# razniffer.net
KiCad netlist of a schematic drawn in EAGLE
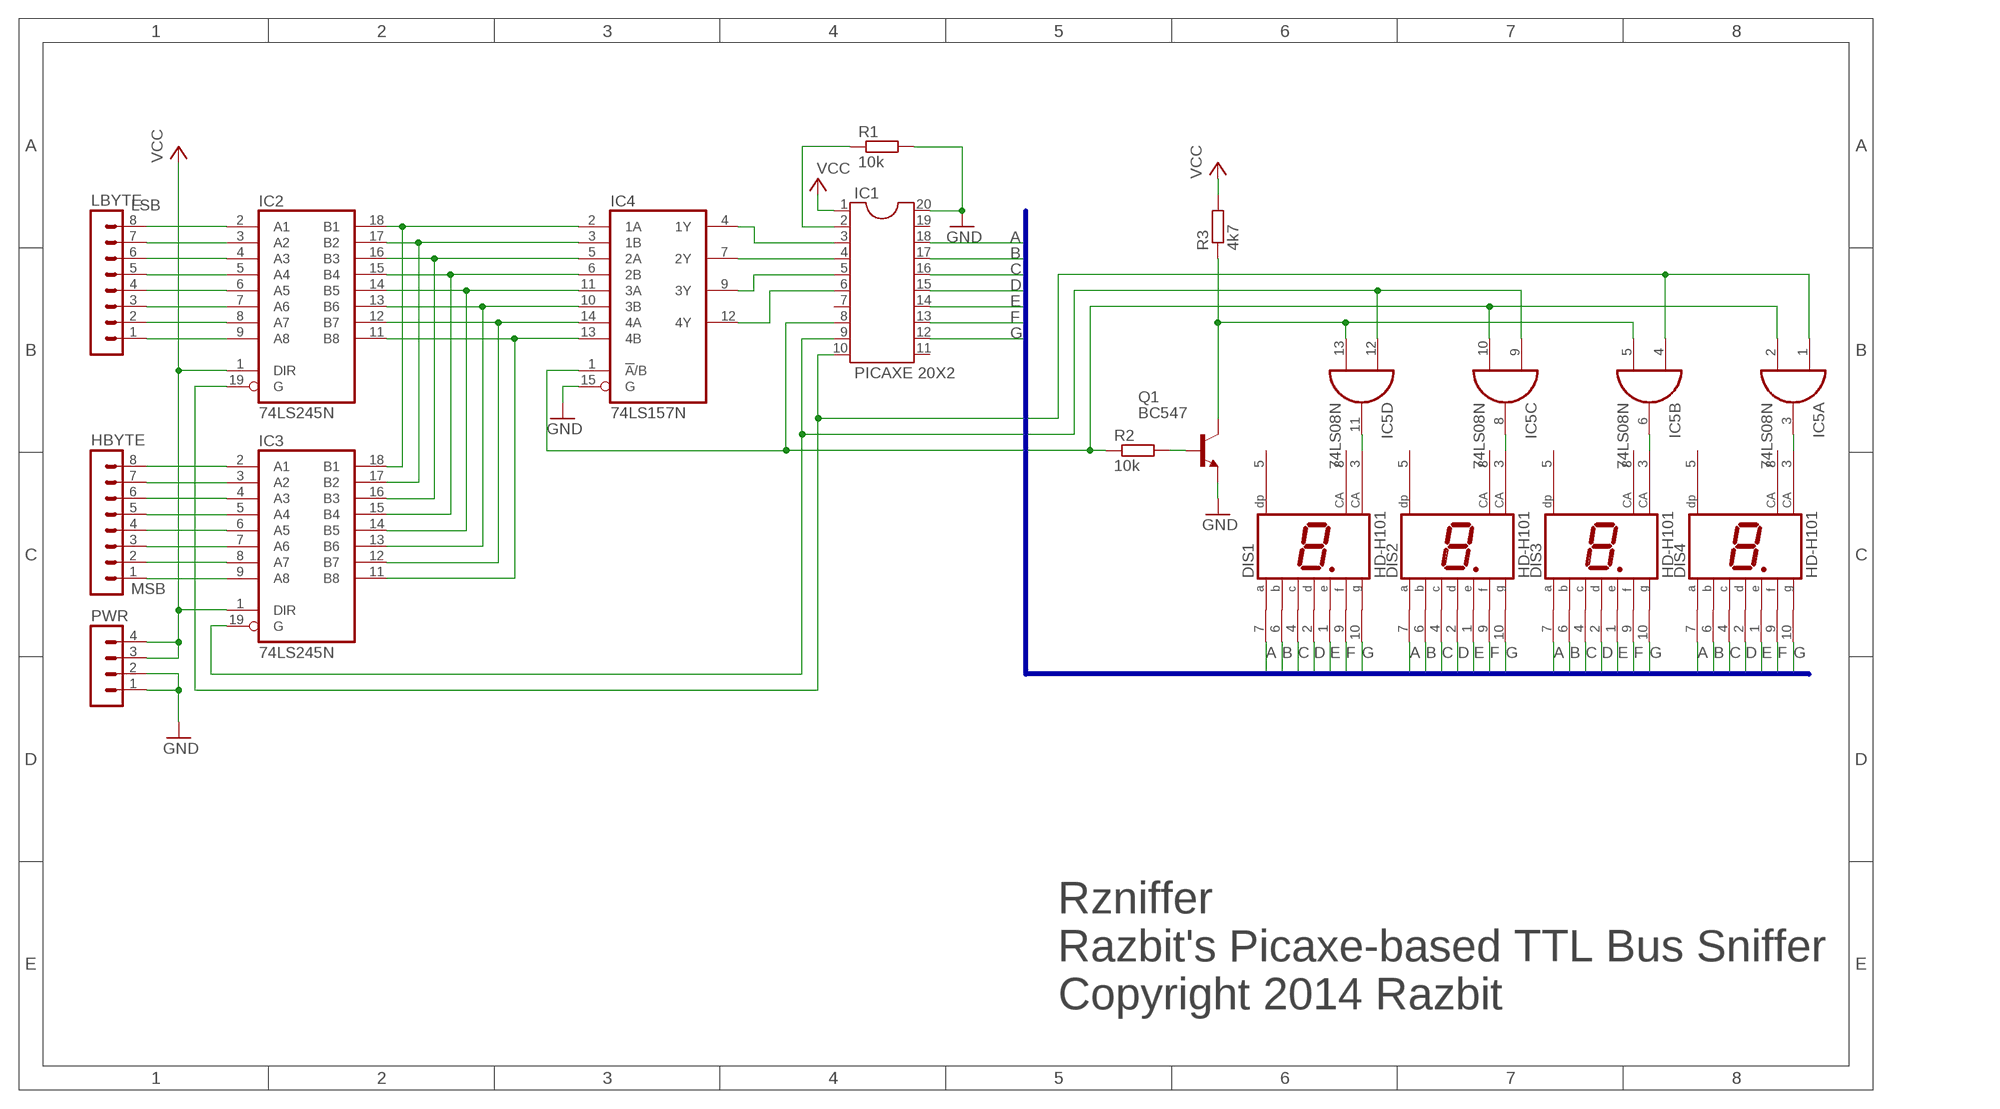
[diagram p0: schematic, sheet 1]

(export (version "E")
  (design (tool "Eeschema 10.0.6"))
  (components
    (comp (ref "DIS1")
      (value "HD-H101")
      (footprint "eagle-import:HDSP-M")
      (libsource (lib "eagle-import") (part "HD-H101"))
    )
    (comp (ref "DIS2")
      (value "HD-H101")
      (footprint "eagle-import:HDSP-M")
      (libsource (lib "eagle-import") (part "HD-H101"))
    )
    (comp (ref "DIS3")
      (value "HD-H101")
      (footprint "eagle-import:HDSP-M")
      (libsource (lib "eagle-import") (part "HD-H101"))
    )
    (comp (ref "DIS4")
      (value "HD-H101")
      (footprint "eagle-import:HDSP-M")
      (libsource (lib "eagle-import") (part "HD-H101"))
    )
    (comp (ref "HBYTE")
      (value "MA08-1")
      (footprint "eagle-import:MA08-1")
      (libsource (lib "eagle-import") (part "MA08-1"))
    )
    (comp (ref "IC1")
      (value "PICAXE 20X2")
      (footprint "eagle-import:DIL20")
      (libsource (lib "eagle-import") (part "DIL20"))
    )
    (comp (ref "IC2")
      (value "74LS245N")
      (footprint "eagle-import:DIL20")
      (libsource (lib "eagle-import") (part "74245NLS"))
    )
    (comp (ref "IC3")
      (value "74LS245N")
      (footprint "eagle-import:DIL20")
      (libsource (lib "eagle-import") (part "74245NLS"))
    )
    (comp (ref "IC4")
      (value "74LS157N")
      (footprint "eagle-import:DIL16")
      (libsource (lib "eagle-import") (part "74157NLS"))
    )
    (comp (ref "IC5")
      (value "74LS08N")
      (footprint "eagle-import:DIL14")
      (libsource (lib "eagle-import") (part "7408NLS"))
    )
    (comp (ref "LBYTE")
      (value "MA08-1")
      (footprint "eagle-import:MA08-1")
      (libsource (lib "eagle-import") (part "MA08-1"))
    )
    (comp (ref "PWR")
      (value "MA04-1")
      (footprint "eagle-import:MA04-1")
      (libsource (lib "eagle-import") (part "MA04-1"))
    )
    (comp (ref "Q1")
      (value "BC547")
      (footprint "eagle-import:TO92")
      (libsource (lib "eagle-import") (part "BC547"))
    )
    (comp (ref "R1")
      (value "10k")
      (footprint "eagle-import:0204_7")
      (libsource (lib "eagle-import") (part "R-EU_0204/7"))
    )
    (comp (ref "R2")
      (value "10k")
      (footprint "eagle-import:0204_7")
      (libsource (lib "eagle-import") (part "R-EU_0204/7"))
    )
    (comp (ref "R3")
      (value "4k7")
      (footprint "eagle-import:0204_7")
      (libsource (lib "eagle-import") (part "R-EU_0204/7"))
    )
  )
  (nets
    (net (code "1") (name "/A") (class "Default")
      (node (ref "DIS1") (pin "7") (pinfunction "A_7") (pintype "passive"))
      (node (ref "DIS2") (pin "7") (pinfunction "A_7") (pintype "passive"))
      (node (ref "DIS3") (pin "7") (pinfunction "A_7") (pintype "passive"))
      (node (ref "DIS4") (pin "7") (pinfunction "A_7") (pintype "passive"))
      (node (ref "IC1") (pin "18") (pinfunction "18_18") (pintype "passive"))
    )
    (net (code "2") (name "/B") (class "Default")
      (node (ref "DIS1") (pin "6") (pinfunction "B_6") (pintype "passive"))
      (node (ref "DIS2") (pin "6") (pinfunction "B_6") (pintype "passive"))
      (node (ref "DIS3") (pin "6") (pinfunction "B_6") (pintype "passive"))
      (node (ref "DIS4") (pin "6") (pinfunction "B_6") (pintype "passive"))
      (node (ref "IC1") (pin "17") (pinfunction "17_17") (pintype "passive"))
    )
    (net (code "3") (name "/C") (class "Default")
      (node (ref "DIS1") (pin "4") (pinfunction "C_4") (pintype "passive"))
      (node (ref "DIS2") (pin "4") (pinfunction "C_4") (pintype "passive"))
      (node (ref "DIS3") (pin "4") (pinfunction "C_4") (pintype "passive"))
      (node (ref "DIS4") (pin "4") (pinfunction "C_4") (pintype "passive"))
      (node (ref "IC1") (pin "16") (pinfunction "16_16") (pintype "passive"))
    )
    (net (code "4") (name "/D") (class "Default")
      (node (ref "DIS1") (pin "2") (pinfunction "D_2") (pintype "passive"))
      (node (ref "DIS2") (pin "2") (pinfunction "D_2") (pintype "passive"))
      (node (ref "DIS3") (pin "2") (pinfunction "D_2") (pintype "passive"))
      (node (ref "DIS4") (pin "2") (pinfunction "D_2") (pintype "passive"))
      (node (ref "IC1") (pin "15") (pinfunction "15_15") (pintype "passive"))
    )
    (net (code "5") (name "/E") (class "Default")
      (node (ref "DIS1") (pin "1") (pinfunction "E_1") (pintype "passive"))
      (node (ref "DIS2") (pin "1") (pinfunction "E_1") (pintype "passive"))
      (node (ref "DIS3") (pin "1") (pinfunction "E_1") (pintype "passive"))
      (node (ref "DIS4") (pin "1") (pinfunction "E_1") (pintype "passive"))
      (node (ref "IC1") (pin "14") (pinfunction "14_14") (pintype "passive"))
    )
    (net (code "6") (name "/F") (class "Default")
      (node (ref "DIS1") (pin "9") (pinfunction "F_9") (pintype "passive"))
      (node (ref "DIS2") (pin "9") (pinfunction "F_9") (pintype "passive"))
      (node (ref "DIS3") (pin "9") (pinfunction "F_9") (pintype "passive"))
      (node (ref "DIS4") (pin "9") (pinfunction "F_9") (pintype "passive"))
      (node (ref "IC1") (pin "13") (pinfunction "13_13") (pintype "passive"))
    )
    (net (code "7") (name "/G") (class "Default")
      (node (ref "DIS1") (pin "10") (pinfunction "G_10") (pintype "passive"))
      (node (ref "DIS2") (pin "10") (pinfunction "G_10") (pintype "passive"))
      (node (ref "DIS3") (pin "10") (pinfunction "G_10") (pintype "passive"))
      (node (ref "DIS4") (pin "10") (pinfunction "G_10") (pintype "passive"))
      (node (ref "IC1") (pin "12") (pinfunction "12_12") (pintype "passive"))
    )
    (net (code "8") (name "GND") (class "Default")
      (node (ref "IC1") (pin "20") (pinfunction "20_20") (pintype "passive"))
      (node (ref "IC4") (pin "15") (pinfunction "G_15") (pintype "input"))
      (node (ref "PWR") (pin "1") (pinfunction "1_1") (pintype "passive"))
      (node (ref "PWR") (pin "2") (pinfunction "2_2") (pintype "passive"))
      (node (ref "Q1") (pin "1") (pinfunction "E_1") (pintype "passive"))
      (node (ref "R1") (pin "2") (pinfunction "2_2") (pintype "passive"))
    )
    (net (code "9") (name "Net-(IC1-Pad2)") (class "Default")
      (node (ref "IC1") (pin "2") (pinfunction "2_2") (pintype "passive"))
      (node (ref "R1") (pin "1") (pinfunction "1_1") (pintype "passive"))
    )
    (net (code "10") (name "Net-(IC2A-A1)") (class "Default")
      (node (ref "IC2") (pin "2") (pinfunction "A1_2") (pintype "bidirectional"))
      (node (ref "LBYTE") (pin "8") (pinfunction "8_8") (pintype "passive"))
    )
    (net (code "11") (name "Net-(IC2A-A2)") (class "Default")
      (node (ref "IC2") (pin "3") (pinfunction "A2_3") (pintype "bidirectional"))
      (node (ref "LBYTE") (pin "7") (pinfunction "7_7") (pintype "passive"))
    )
    (net (code "12") (name "Net-(IC2A-A3)") (class "Default")
      (node (ref "IC2") (pin "4") (pinfunction "A3_4") (pintype "bidirectional"))
      (node (ref "LBYTE") (pin "6") (pinfunction "6_6") (pintype "passive"))
    )
    (net (code "13") (name "Net-(IC2A-A4)") (class "Default")
      (node (ref "IC2") (pin "5") (pinfunction "A4_5") (pintype "bidirectional"))
      (node (ref "LBYTE") (pin "5") (pinfunction "5_5") (pintype "passive"))
    )
    (net (code "14") (name "Net-(IC2A-A5)") (class "Default")
      (node (ref "IC2") (pin "6") (pinfunction "A5_6") (pintype "bidirectional"))
      (node (ref "LBYTE") (pin "4") (pinfunction "4_4") (pintype "passive"))
    )
    (net (code "15") (name "Net-(IC2A-A6)") (class "Default")
      (node (ref "IC2") (pin "7") (pinfunction "A6_7") (pintype "bidirectional"))
      (node (ref "LBYTE") (pin "3") (pinfunction "3_3") (pintype "passive"))
    )
    (net (code "16") (name "Net-(IC2A-A7)") (class "Default")
      (node (ref "IC2") (pin "8") (pinfunction "A7_8") (pintype "bidirectional"))
      (node (ref "LBYTE") (pin "2") (pinfunction "2_2") (pintype "passive"))
    )
    (net (code "17") (name "Net-(IC2A-A8)") (class "Default")
      (node (ref "IC2") (pin "9") (pinfunction "A8_9") (pintype "bidirectional"))
      (node (ref "LBYTE") (pin "1") (pinfunction "1_1") (pintype "passive"))
    )
    (net (code "18") (name "Net-(IC2A-B1)") (class "Default")
      (node (ref "IC2") (pin "18") (pinfunction "B1_18") (pintype "bidirectional"))
      (node (ref "IC3") (pin "18") (pinfunction "B1_18") (pintype "bidirectional"))
      (node (ref "IC4") (pin "2") (pinfunction "1A_2") (pintype "input"))
    )
    (net (code "19") (name "Net-(IC2A-B2)") (class "Default")
      (node (ref "IC2") (pin "17") (pinfunction "B2_17") (pintype "bidirectional"))
      (node (ref "IC3") (pin "17") (pinfunction "B2_17") (pintype "bidirectional"))
      (node (ref "IC4") (pin "3") (pinfunction "1B_3") (pintype "input"))
    )
    (net (code "20") (name "Net-(IC2A-B3)") (class "Default")
      (node (ref "IC2") (pin "16") (pinfunction "B3_16") (pintype "bidirectional"))
      (node (ref "IC3") (pin "16") (pinfunction "B3_16") (pintype "bidirectional"))
      (node (ref "IC4") (pin "5") (pinfunction "2A_5") (pintype "input"))
    )
    (net (code "21") (name "Net-(IC2A-B4)") (class "Default")
      (node (ref "IC2") (pin "15") (pinfunction "B4_15") (pintype "bidirectional"))
      (node (ref "IC3") (pin "15") (pinfunction "B4_15") (pintype "bidirectional"))
      (node (ref "IC4") (pin "6") (pinfunction "2B_6") (pintype "input"))
    )
    (net (code "22") (name "Net-(IC2A-B5)") (class "Default")
      (node (ref "IC2") (pin "14") (pinfunction "B5_14") (pintype "bidirectional"))
      (node (ref "IC3") (pin "14") (pinfunction "B5_14") (pintype "bidirectional"))
      (node (ref "IC4") (pin "11") (pinfunction "3A_11") (pintype "input"))
    )
    (net (code "23") (name "Net-(IC2A-B6)") (class "Default")
      (node (ref "IC2") (pin "13") (pinfunction "B6_13") (pintype "bidirectional"))
      (node (ref "IC3") (pin "13") (pinfunction "B6_13") (pintype "bidirectional"))
      (node (ref "IC4") (pin "10") (pinfunction "3B_10") (pintype "input"))
    )
    (net (code "24") (name "Net-(IC2A-B7)") (class "Default")
      (node (ref "IC2") (pin "12") (pinfunction "B7_12") (pintype "bidirectional"))
      (node (ref "IC3") (pin "12") (pinfunction "B7_12") (pintype "bidirectional"))
      (node (ref "IC4") (pin "14") (pinfunction "4A_14") (pintype "input"))
    )
    (net (code "25") (name "Net-(IC2A-B8)") (class "Default")
      (node (ref "IC2") (pin "11") (pinfunction "B8_11") (pintype "bidirectional"))
      (node (ref "IC3") (pin "11") (pinfunction "B8_11") (pintype "bidirectional"))
      (node (ref "IC4") (pin "13") (pinfunction "4B_13") (pintype "input"))
    )
    (net (code "26") (name "Net-(IC2A-G)") (class "Default")
      (node (ref "IC1") (pin "10") (pinfunction "10_10") (pintype "passive"))
      (node (ref "IC2") (pin "19") (pinfunction "G_19") (pintype "input"))
      (node (ref "IC5") (pin "1") (pinfunction "I0_1") (pintype "input"))
      (node (ref "IC5") (pin "4") (pinfunction "I0_4") (pintype "input"))
    )
    (net (code "27") (name "Net-(IC3A-A1)") (class "Default")
      (node (ref "HBYTE") (pin "8") (pinfunction "8_8") (pintype "passive"))
      (node (ref "IC3") (pin "2") (pinfunction "A1_2") (pintype "bidirectional"))
    )
    (net (code "28") (name "Net-(IC3A-A2)") (class "Default")
      (node (ref "HBYTE") (pin "7") (pinfunction "7_7") (pintype "passive"))
      (node (ref "IC3") (pin "3") (pinfunction "A2_3") (pintype "bidirectional"))
    )
    (net (code "29") (name "Net-(IC3A-A3)") (class "Default")
      (node (ref "HBYTE") (pin "6") (pinfunction "6_6") (pintype "passive"))
      (node (ref "IC3") (pin "4") (pinfunction "A3_4") (pintype "bidirectional"))
    )
    (net (code "30") (name "Net-(IC3A-A4)") (class "Default")
      (node (ref "HBYTE") (pin "5") (pinfunction "5_5") (pintype "passive"))
      (node (ref "IC3") (pin "5") (pinfunction "A4_5") (pintype "bidirectional"))
    )
    (net (code "31") (name "Net-(IC3A-A5)") (class "Default")
      (node (ref "HBYTE") (pin "4") (pinfunction "4_4") (pintype "passive"))
      (node (ref "IC3") (pin "6") (pinfunction "A5_6") (pintype "bidirectional"))
    )
    (net (code "32") (name "Net-(IC3A-A6)") (class "Default")
      (node (ref "HBYTE") (pin "3") (pinfunction "3_3") (pintype "passive"))
      (node (ref "IC3") (pin "7") (pinfunction "A6_7") (pintype "bidirectional"))
    )
    (net (code "33") (name "Net-(IC3A-A7)") (class "Default")
      (node (ref "HBYTE") (pin "2") (pinfunction "2_2") (pintype "passive"))
      (node (ref "IC3") (pin "8") (pinfunction "A7_8") (pintype "bidirectional"))
    )
    (net (code "34") (name "Net-(IC3A-A8)") (class "Default")
      (node (ref "HBYTE") (pin "1") (pinfunction "1_1") (pintype "passive"))
      (node (ref "IC3") (pin "9") (pinfunction "A8_9") (pintype "bidirectional"))
    )
    (net (code "35") (name "Net-(IC3A-G)") (class "Default")
      (node (ref "IC1") (pin "9") (pinfunction "9_9") (pintype "passive"))
      (node (ref "IC3") (pin "19") (pinfunction "G_19") (pintype "input"))
      (node (ref "IC5") (pin "12") (pinfunction "I0_12") (pintype "input"))
      (node (ref "IC5") (pin "9") (pinfunction "I0_9") (pintype "input"))
    )
    (net (code "36") (name "Net-(IC4A-1Y)") (class "Default")
      (node (ref "IC1") (pin "3") (pinfunction "3_3") (pintype "passive"))
      (node (ref "IC4") (pin "4") (pinfunction "1Y_4") (pintype "output"))
    )
    (net (code "37") (name "Net-(IC4A-2Y)") (class "Default")
      (node (ref "IC1") (pin "4") (pinfunction "4_4") (pintype "passive"))
      (node (ref "IC4") (pin "7") (pinfunction "2Y_7") (pintype "output"))
    )
    (net (code "38") (name "Net-(IC4A-3Y)") (class "Default")
      (node (ref "IC1") (pin "5") (pinfunction "5_5") (pintype "passive"))
      (node (ref "IC4") (pin "9") (pinfunction "3Y_9") (pintype "output"))
    )
    (net (code "39") (name "Net-(IC4A-4Y)") (class "Default")
      (node (ref "IC1") (pin "6") (pinfunction "6_6") (pintype "passive"))
      (node (ref "IC4") (pin "12") (pinfunction "4Y_12") (pintype "output"))
    )
    (net (code "40") (name "Net-(IC4A-~{A}{slash}B)") (class "Default")
      (node (ref "IC1") (pin "8") (pinfunction "8_8") (pintype "passive"))
      (node (ref "IC4") (pin "1") (pinfunction "~{A}/B_1") (pintype "input"))
      (node (ref "IC5") (pin "10") (pinfunction "I1_10") (pintype "input"))
      (node (ref "IC5") (pin "2") (pinfunction "I1_2") (pintype "input"))
      (node (ref "R2") (pin "1") (pinfunction "1_1") (pintype "passive"))
    )
    (net (code "41") (name "Net-(IC5A-O)") (class "Default")
      (node (ref "DIS4") (pin "3") (pinfunction "CA_3") (pintype "passive"))
      (node (ref "IC5") (pin "3") (pinfunction "O_3") (pintype "output"))
    )
    (net (code "42") (name "Net-(IC5B-I1)") (class "Default")
      (node (ref "IC5") (pin "13") (pinfunction "I1_13") (pintype "input"))
      (node (ref "IC5") (pin "5") (pinfunction "I1_5") (pintype "input"))
      (node (ref "Q1") (pin "3") (pinfunction "C_3") (pintype "passive"))
      (node (ref "R3") (pin "1") (pinfunction "1_1") (pintype "passive"))
    )
    (net (code "43") (name "Net-(IC5B-O)") (class "Default")
      (node (ref "DIS3") (pin "3") (pinfunction "CA_3") (pintype "passive"))
      (node (ref "IC5") (pin "6") (pinfunction "O_6") (pintype "output"))
    )
    (net (code "44") (name "Net-(IC5C-O)") (class "Default")
      (node (ref "DIS2") (pin "3") (pinfunction "CA_3") (pintype "passive"))
      (node (ref "IC5") (pin "8") (pinfunction "O_8") (pintype "output"))
    )
    (net (code "45") (name "Net-(IC5D-O)") (class "Default")
      (node (ref "DIS1") (pin "3") (pinfunction "CA_3") (pintype "passive"))
      (node (ref "IC5") (pin "11") (pinfunction "O_11") (pintype "output"))
    )
    (net (code "46") (name "Net-(Q1-B)") (class "Default")
      (node (ref "Q1") (pin "2") (pinfunction "B_2") (pintype "passive"))
      (node (ref "R2") (pin "2") (pinfunction "2_2") (pintype "passive"))
    )
    (net (code "47") (name "VCC") (class "Default")
      (node (ref "IC1") (pin "1") (pinfunction "1_1") (pintype "passive"))
      (node (ref "IC2") (pin "1") (pinfunction "DIR_1") (pintype "input"))
      (node (ref "IC3") (pin "1") (pinfunction "DIR_1") (pintype "input"))
      (node (ref "PWR") (pin "3") (pinfunction "3_3") (pintype "passive"))
      (node (ref "PWR") (pin "4") (pinfunction "4_4") (pintype "passive"))
      (node (ref "R3") (pin "2") (pinfunction "2_2") (pintype "passive"))
    )
    (net (code "48") (name "unconnected-(DIS1-CA-Pad8)") (class "Default")
      (node (ref "DIS1") (pin "8") (pinfunction "CA_8") (pintype "passive"))
    )
    (net (code "49") (name "unconnected-(DIS1-DP-Pad5)") (class "Default")
      (node (ref "DIS1") (pin "5") (pinfunction "DP_5") (pintype "passive"))
    )
    (net (code "50") (name "unconnected-(DIS2-CA-Pad8)") (class "Default")
      (node (ref "DIS2") (pin "8") (pinfunction "CA_8") (pintype "passive"))
    )
    (net (code "51") (name "unconnected-(DIS2-DP-Pad5)") (class "Default")
      (node (ref "DIS2") (pin "5") (pinfunction "DP_5") (pintype "passive"))
    )
    (net (code "52") (name "unconnected-(DIS3-CA-Pad8)") (class "Default")
      (node (ref "DIS3") (pin "8") (pinfunction "CA_8") (pintype "passive"))
    )
    (net (code "53") (name "unconnected-(DIS3-DP-Pad5)") (class "Default")
      (node (ref "DIS3") (pin "5") (pinfunction "DP_5") (pintype "passive"))
    )
    (net (code "54") (name "unconnected-(DIS4-CA-Pad8)") (class "Default")
      (node (ref "DIS4") (pin "8") (pinfunction "CA_8") (pintype "passive"))
    )
    (net (code "55") (name "unconnected-(DIS4-DP-Pad5)") (class "Default")
      (node (ref "DIS4") (pin "5") (pinfunction "DP_5") (pintype "passive"))
    )
    (net (code "56") (name "unconnected-(IC1-Pad7)") (class "Default")
      (node (ref "IC1") (pin "7") (pinfunction "7_7") (pintype "passive"))
    )
    (net (code "57") (name "unconnected-(IC1-Pad11)") (class "Default")
      (node (ref "IC1") (pin "11") (pinfunction "11_11") (pintype "passive"))
    )
    (net (code "58") (name "unconnected-(IC1-Pad19)") (class "Default")
      (node (ref "IC1") (pin "19") (pinfunction "19_19") (pintype "passive"))
    )
  )
)
